# IRTx.net
KiCad netlist of a schematic drawn in EAGLE
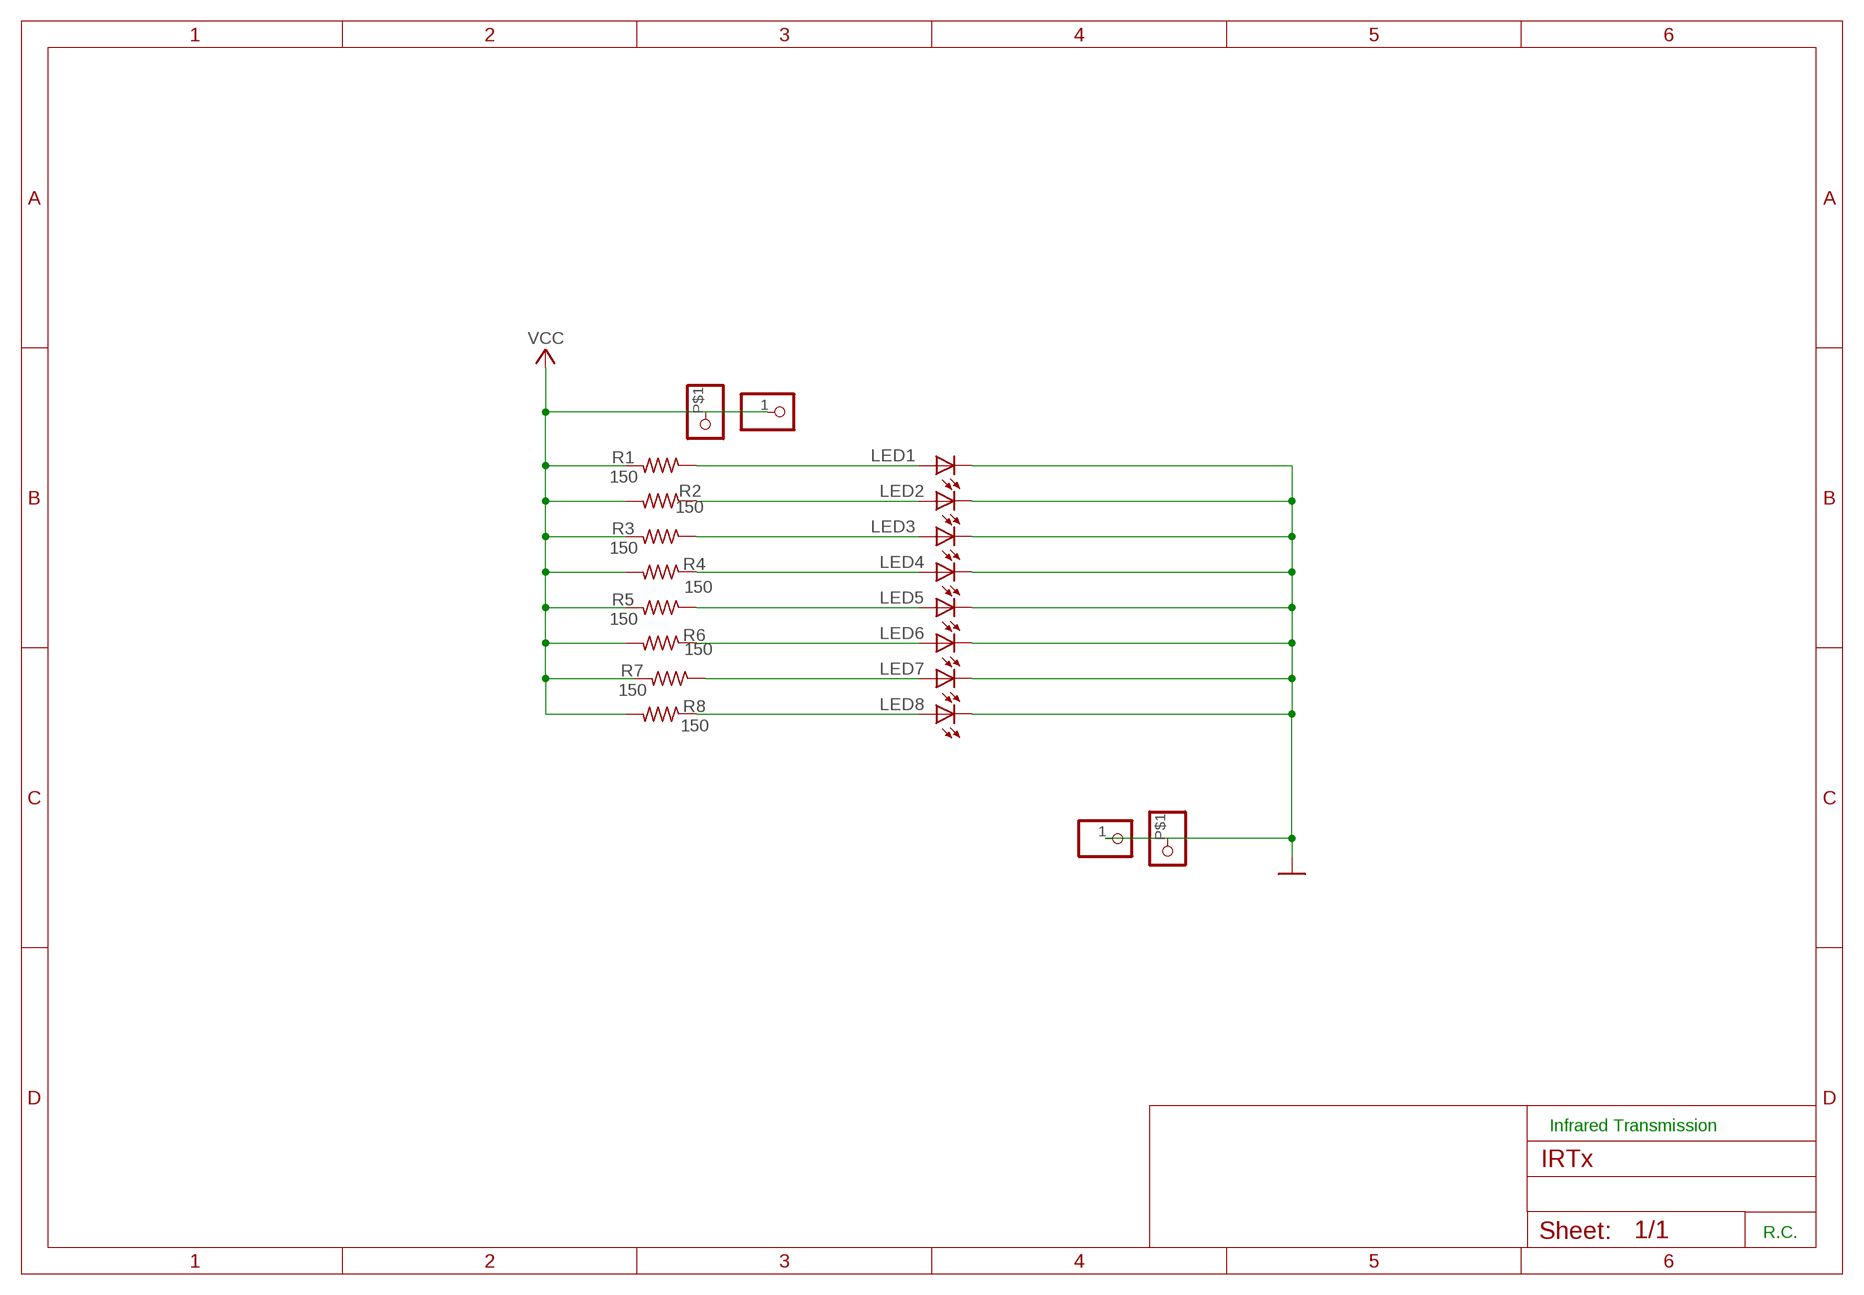
[diagram p0: schematic, sheet 1]

(export (version "E")
  (design (tool "Eeschema 10.0.6"))
  (components
    (comp (ref "JP1")
      (value "3.3")
      (footprint "eagle-import:1X1-BIGPOGO")
      (libsource (lib "eagle-import") (part "PINHD-1X1-BIGPOGO"))
    )
    (comp (ref "JP2")
      (value "GND")
      (footprint "eagle-import:1X1-BIGPOGO")
      (libsource (lib "eagle-import") (part "PINHD-1X1-BIGPOGO"))
    )
    (comp (ref "JP3")
      (value "PINHD-1X1")
      (footprint "eagle-import:1X01")
      (libsource (lib "eagle-import") (part "PINHD-1X1"))
    )
    (comp (ref "JP4")
      (value "PINHD-1X1")
      (footprint "eagle-import:1X01")
      (libsource (lib "eagle-import") (part "PINHD-1X1"))
    )
    (comp (ref "LED1")
      (value "LED5MM")
      (footprint "eagle-import:LED5MM")
      (libsource (lib "eagle-import") (part "LED5MM"))
    )
    (comp (ref "LED2")
      (value "LED5MM")
      (footprint "eagle-import:LED5MM")
      (libsource (lib "eagle-import") (part "LED5MM"))
    )
    (comp (ref "LED3")
      (value "LED5MM")
      (footprint "eagle-import:LED5MM")
      (libsource (lib "eagle-import") (part "LED5MM"))
    )
    (comp (ref "LED4")
      (value "LED5MM")
      (footprint "eagle-import:LED5MM")
      (libsource (lib "eagle-import") (part "LED5MM"))
    )
    (comp (ref "LED5")
      (value "LED5MM")
      (footprint "eagle-import:LED5MM")
      (libsource (lib "eagle-import") (part "LED5MM"))
    )
    (comp (ref "LED6")
      (value "LED5MM")
      (footprint "eagle-import:LED5MM")
      (libsource (lib "eagle-import") (part "LED5MM"))
    )
    (comp (ref "LED7")
      (value "LED5MM")
      (footprint "eagle-import:LED5MM")
      (libsource (lib "eagle-import") (part "LED5MM"))
    )
    (comp (ref "LED8")
      (value "LED5MM")
      (footprint "eagle-import:LED5MM")
      (libsource (lib "eagle-import") (part "LED5MM"))
    )
    (comp (ref "R1")
      (value "150")
      (footprint "eagle-import:0207_10")
      (libsource (lib "eagle-import") (part "R-US_0207/10"))
    )
    (comp (ref "R2")
      (value "150")
      (footprint "eagle-import:0207_10")
      (libsource (lib "eagle-import") (part "R-US_0207/10"))
    )
    (comp (ref "R3")
      (value "150")
      (footprint "eagle-import:0207_10")
      (libsource (lib "eagle-import") (part "R-US_0207/10"))
    )
    (comp (ref "R4")
      (value "150")
      (footprint "eagle-import:0207_10")
      (libsource (lib "eagle-import") (part "R-US_0207/10"))
    )
    (comp (ref "R5")
      (value "150")
      (footprint "eagle-import:0207_10")
      (libsource (lib "eagle-import") (part "R-US_0207/10"))
    )
    (comp (ref "R6")
      (value "150")
      (footprint "eagle-import:0207_10")
      (libsource (lib "eagle-import") (part "R-US_0207/10"))
    )
    (comp (ref "R7")
      (value "150")
      (footprint "eagle-import:0207_10")
      (libsource (lib "eagle-import") (part "R-US_0207/10"))
    )
    (comp (ref "R8")
      (value "150")
      (footprint "eagle-import:0207_10")
      (libsource (lib "eagle-import") (part "R-US_0207/10"))
    )
  )
  (nets
    (net (code "1") (name "GND") (class "Default")
      (node (ref "JP2") (pin "P$1") (pinfunction "1_P$1") (pintype "passive"))
      (node (ref "JP4") (pin "1") (pinfunction "1_1") (pintype "passive"))
      (node (ref "LED1") (pin "K") (pinfunction "C_K") (pintype "passive"))
      (node (ref "LED2") (pin "K") (pinfunction "C_K") (pintype "passive"))
      (node (ref "LED3") (pin "K") (pinfunction "C_K") (pintype "passive"))
      (node (ref "LED4") (pin "K") (pinfunction "C_K") (pintype "passive"))
      (node (ref "LED5") (pin "K") (pinfunction "C_K") (pintype "passive"))
      (node (ref "LED6") (pin "K") (pinfunction "C_K") (pintype "passive"))
      (node (ref "LED7") (pin "K") (pinfunction "C_K") (pintype "passive"))
      (node (ref "LED8") (pin "K") (pinfunction "C_K") (pintype "passive"))
    )
    (net (code "2") (name "Net-(LED1-PadA)") (class "Default")
      (node (ref "LED1") (pin "A") (pinfunction "A_A") (pintype "passive"))
      (node (ref "R1") (pin "1") (pinfunction "1_1") (pintype "passive"))
    )
    (net (code "3") (name "Net-(LED2-PadA)") (class "Default")
      (node (ref "LED2") (pin "A") (pinfunction "A_A") (pintype "passive"))
      (node (ref "R2") (pin "1") (pinfunction "1_1") (pintype "passive"))
    )
    (net (code "4") (name "Net-(LED3-PadA)") (class "Default")
      (node (ref "LED3") (pin "A") (pinfunction "A_A") (pintype "passive"))
      (node (ref "R3") (pin "1") (pinfunction "1_1") (pintype "passive"))
    )
    (net (code "5") (name "Net-(LED4-PadA)") (class "Default")
      (node (ref "LED4") (pin "A") (pinfunction "A_A") (pintype "passive"))
      (node (ref "R4") (pin "1") (pinfunction "1_1") (pintype "passive"))
    )
    (net (code "6") (name "Net-(LED5-PadA)") (class "Default")
      (node (ref "LED5") (pin "A") (pinfunction "A_A") (pintype "passive"))
      (node (ref "R5") (pin "1") (pinfunction "1_1") (pintype "passive"))
    )
    (net (code "7") (name "Net-(LED6-PadA)") (class "Default")
      (node (ref "LED6") (pin "A") (pinfunction "A_A") (pintype "passive"))
      (node (ref "R6") (pin "1") (pinfunction "1_1") (pintype "passive"))
    )
    (net (code "8") (name "Net-(LED7-PadA)") (class "Default")
      (node (ref "LED7") (pin "A") (pinfunction "A_A") (pintype "passive"))
      (node (ref "R7") (pin "1") (pinfunction "1_1") (pintype "passive"))
    )
    (net (code "9") (name "Net-(LED8-PadA)") (class "Default")
      (node (ref "LED8") (pin "A") (pinfunction "A_A") (pintype "passive"))
      (node (ref "R8") (pin "1") (pinfunction "1_1") (pintype "passive"))
    )
    (net (code "10") (name "VCC") (class "Default")
      (node (ref "JP1") (pin "P$1") (pinfunction "1_P$1") (pintype "passive"))
      (node (ref "JP3") (pin "1") (pinfunction "1_1") (pintype "passive"))
      (node (ref "R1") (pin "2") (pinfunction "2_2") (pintype "passive"))
      (node (ref "R2") (pin "2") (pinfunction "2_2") (pintype "passive"))
      (node (ref "R3") (pin "2") (pinfunction "2_2") (pintype "passive"))
      (node (ref "R4") (pin "2") (pinfunction "2_2") (pintype "passive"))
      (node (ref "R5") (pin "2") (pinfunction "2_2") (pintype "passive"))
      (node (ref "R6") (pin "2") (pinfunction "2_2") (pintype "passive"))
      (node (ref "R7") (pin "2") (pinfunction "2_2") (pintype "passive"))
      (node (ref "R8") (pin "2") (pinfunction "2_2") (pintype "passive"))
    )
  )
)
